# hal-sensor.net
KiCad netlist of a schematic drawn in EAGLE
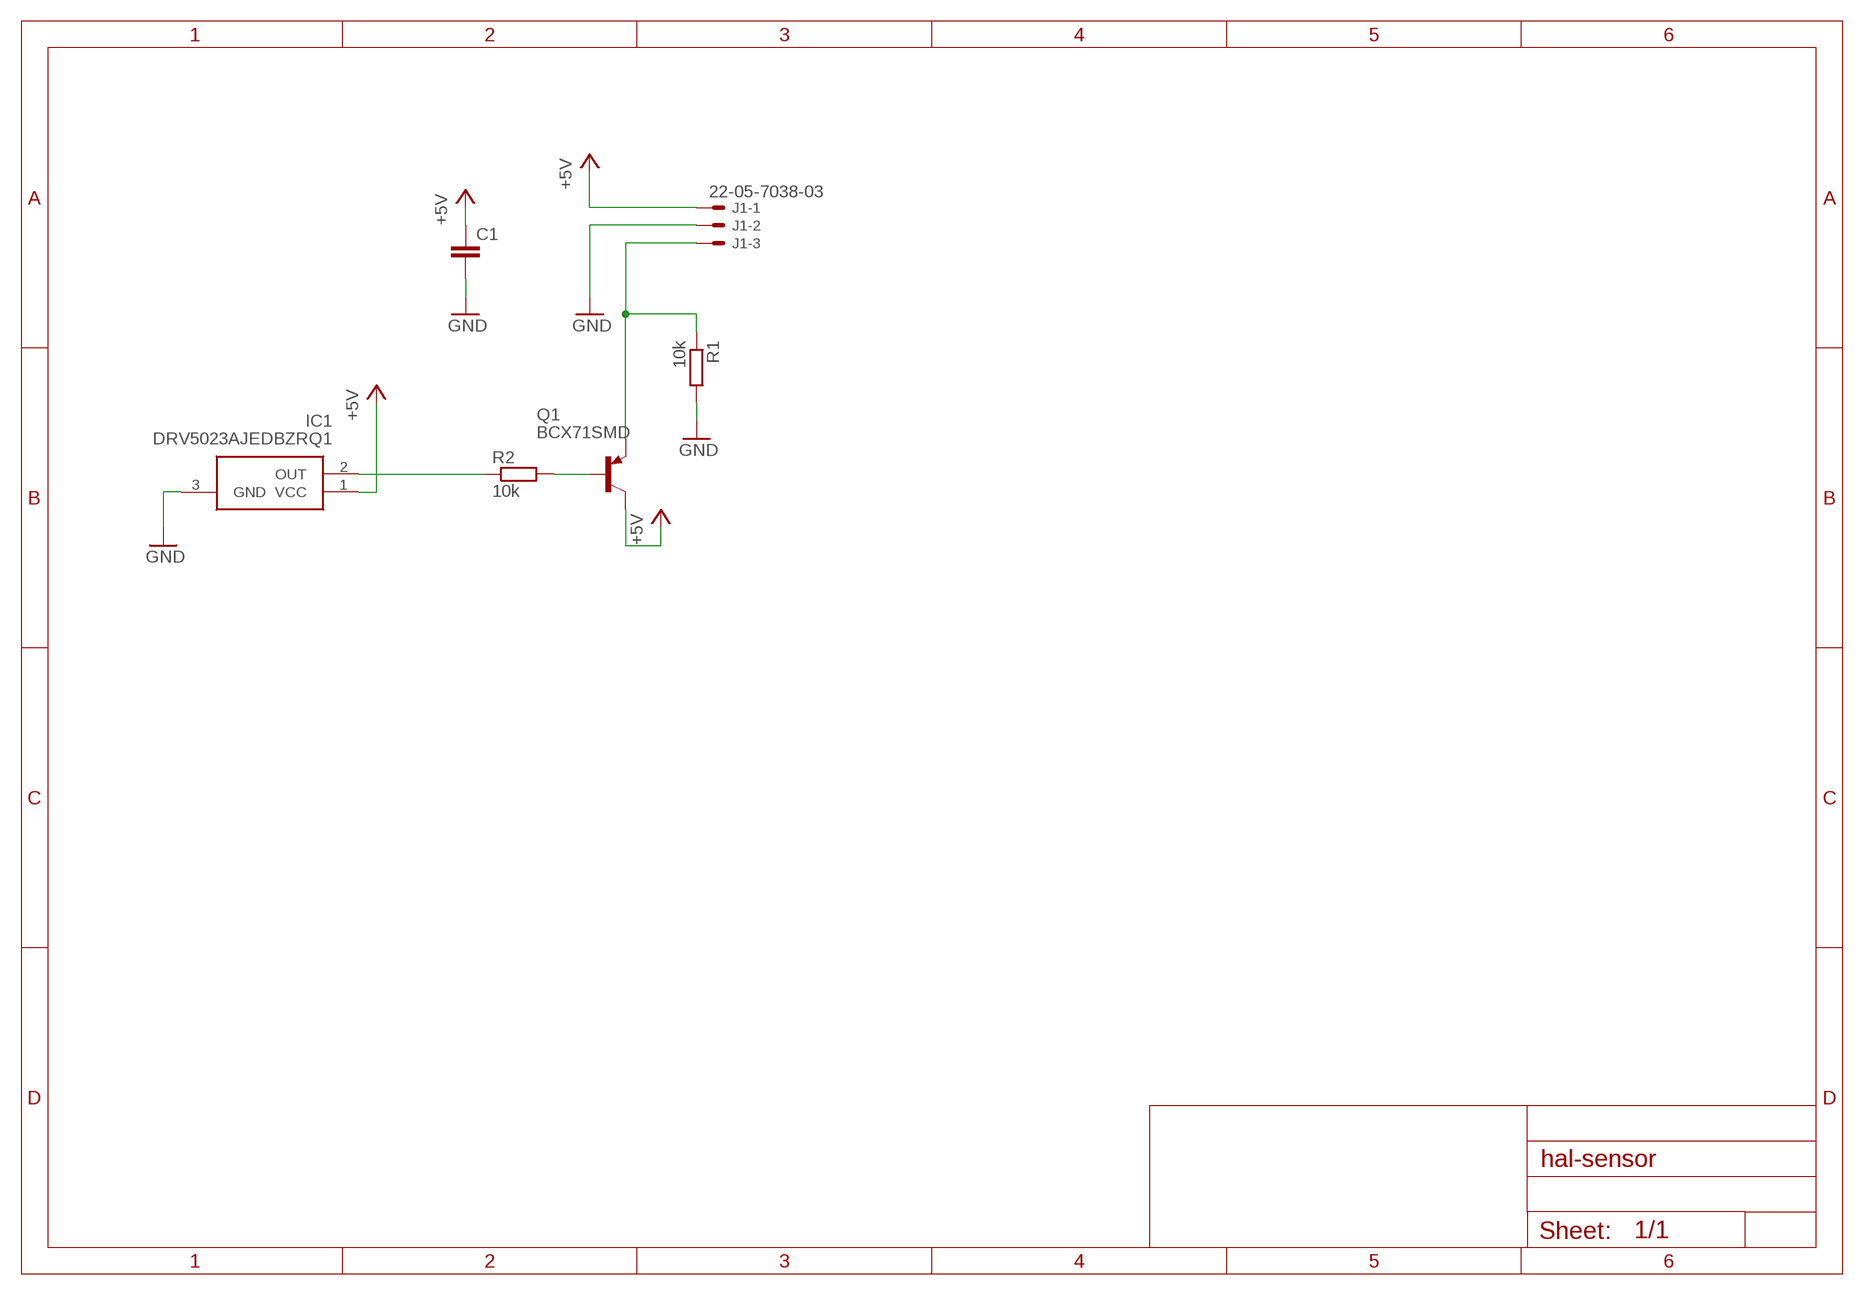
[diagram p0: schematic, sheet 1]

(export (version "E")
  (design (tool "Eeschema 10.0.6"))
  (components
    (comp (ref "C1")
      (value "C-EUC0805")
      (footprint "eagle-import:C0805")
      (libsource (lib "eagle-import") (part "C-EUC0805"))
    )
    (comp (ref "IC1")
      (value "DRV5023AJEDBZRQ1")
      (footprint "eagle-import:SOT95P237X112-3N")
      (fields (field (name "MOUSER_PART_NUMBER") "595-DRV5023AJEDBZRQ1"))
      (libsource (lib "eagle-import") (part "DRV5023AJEDBZRQ1"))
    )
    (comp (ref "J1")
      (value "22-05-7038-03")
      (footprint "eagle-import:7395-03")
      (fields (field (name "MF") "MOLEX"))
      (libsource (lib "eagle-import") (part "22-?-0305-7038"))
    )
    (comp (ref "Q1")
      (value "BCX71SMD")
      (footprint "eagle-import:SOT23")
      (libsource (lib "eagle-import") (part "BCX71SMD"))
    )
    (comp (ref "R1")
      (value "10k")
      (footprint "eagle-import:R0805")
      (libsource (lib "eagle-import") (part "R-EU_R0805"))
    )
    (comp (ref "R2")
      (value "10k")
      (footprint "eagle-import:R0805")
      (libsource (lib "eagle-import") (part "R-EU_R0805"))
    )
  )
  (nets
    (net (code "1") (name "+5V") (class "Default")
      (node (ref "C1") (pin "1") (pinfunction "1_1") (pintype "passive"))
      (node (ref "IC1") (pin "1") (pinfunction "VCC_1") (pintype "bidirectional"))
      (node (ref "J1") (pin "1") (pinfunction "S_1") (pintype "passive"))
      (node (ref "Q1") (pin "3") (pinfunction "C_3") (pintype "passive"))
    )
    (net (code "2") (name "GND") (class "Default")
      (node (ref "C1") (pin "2") (pinfunction "2_2") (pintype "passive"))
      (node (ref "IC1") (pin "3") (pinfunction "GND_3") (pintype "bidirectional"))
      (node (ref "J1") (pin "2") (pinfunction "S_2") (pintype "passive"))
      (node (ref "R1") (pin "2") (pinfunction "2_2") (pintype "passive"))
    )
    (net (code "3") (name "Net-(IC1-OUT)") (class "Default")
      (node (ref "IC1") (pin "2") (pinfunction "OUT_2") (pintype "bidirectional"))
      (node (ref "R2") (pin "1") (pinfunction "1_1") (pintype "passive"))
    )
    (net (code "4") (name "Net-(J1C-S)") (class "Default")
      (node (ref "J1") (pin "3") (pinfunction "S_3") (pintype "passive"))
      (node (ref "Q1") (pin "2") (pinfunction "E_2") (pintype "passive"))
      (node (ref "R1") (pin "1") (pinfunction "1_1") (pintype "passive"))
    )
    (net (code "5") (name "Net-(Q1-B)") (class "Default")
      (node (ref "Q1") (pin "1") (pinfunction "B_1") (pintype "passive"))
      (node (ref "R2") (pin "2") (pinfunction "2_2") (pintype "passive"))
    )
  )
)
